# led_RGB.net
KiCad netlist of a schematic drawn in Altium Designer
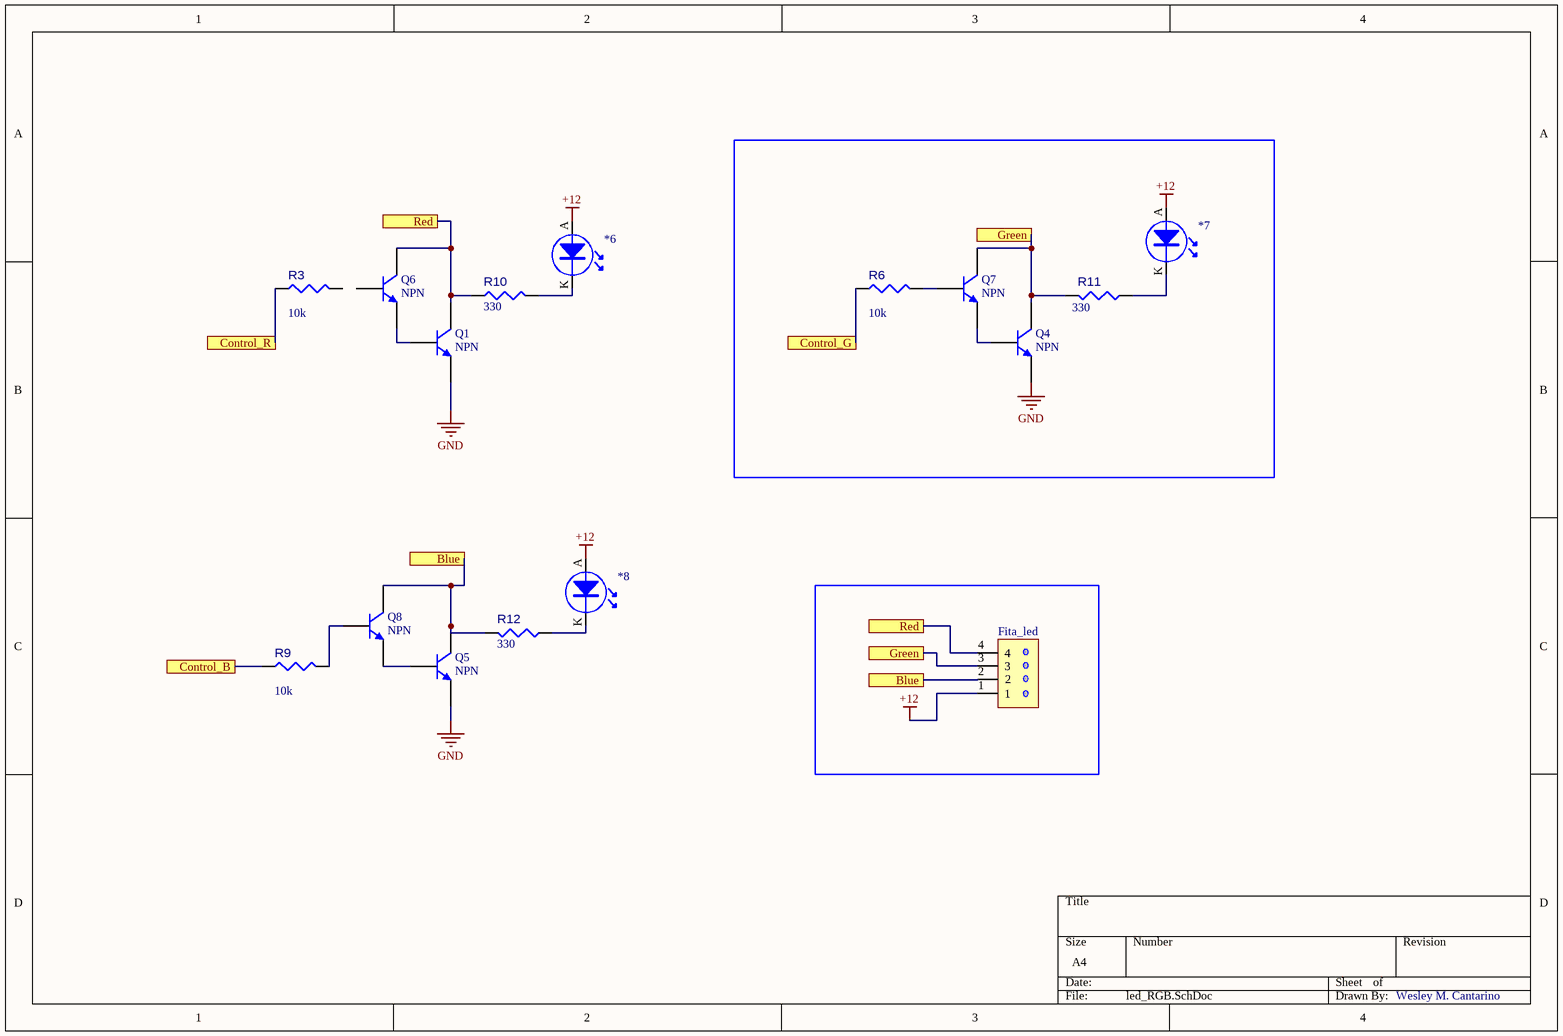
[diagram p0: led_RGB.SchDoc]

(export (version "E")
  (design (tool "Eeschema 10.0.6"))
  (components
    (comp (ref "*6")
      (value "LED_AXIAL_5MM")
      (footprint "HEADER_1X2")
      (libsource (lib "i9Library_Altium") (part "LED_AXIAL_5MM"))
    )
    (comp (ref "*7")
      (value "LED_AXIAL_5MM")
      (footprint "HEADER_1X2")
      (libsource (lib "i9Library_Altium") (part "LED_AXIAL_5MM"))
    )
    (comp (ref "*8")
      (value "LED_AXIAL_5MM")
      (footprint "HEADER_1X2")
      (libsource (lib "i9Library_Altium") (part "LED_AXIAL_5MM"))
    )
    (comp (ref "Fita_led")
      (value "CN_KK_4")
      (footprint "CN_KK_4_5045-4")
      (description "KK_4")
      (libsource (lib "i9Library_Altium") (part "CN_KK_4"))
    )
    (comp (ref "Q1")
      (value "NPN")
      (footprint "HEADER_1X3")
      (description "NPN Bipolar Transistor")
      (fields (field (name "PUBLISHER") "Altium Limited"))
      (libsource (lib "Miscellaneous Devices") (part "NPN"))
    )
    (comp (ref "Q4")
      (value "NPN")
      (footprint "HEADER_1X3")
      (description "NPN Bipolar Transistor")
      (fields (field (name "PUBLISHER") "Altium Limited"))
      (libsource (lib "Miscellaneous Devices") (part "NPN"))
    )
    (comp (ref "Q5")
      (value "NPN")
      (footprint "HEADER_1X3")
      (description "NPN Bipolar Transistor")
      (fields (field (name "PUBLISHER") "Altium Limited"))
      (libsource (lib "Miscellaneous Devices") (part "NPN"))
    )
    (comp (ref "Q6")
      (value "NPN")
      (footprint "HEADER_1X3")
      (description "NPN Bipolar Transistor")
      (fields (field (name "PUBLISHER") "Altium Limited"))
      (libsource (lib "Miscellaneous Devices") (part "NPN"))
    )
    (comp (ref "Q7")
      (value "NPN")
      (footprint "HEADER_1X3")
      (description "NPN Bipolar Transistor")
      (fields (field (name "PUBLISHER") "Altium Limited"))
      (libsource (lib "Miscellaneous Devices") (part "NPN"))
    )
    (comp (ref "Q8")
      (value "NPN")
      (footprint "HEADER_1X3")
      (description "NPN Bipolar Transistor")
      (fields (field (name "PUBLISHER") "Altium Limited"))
      (libsource (lib "Miscellaneous Devices") (part "NPN"))
    )
    (comp (ref "R3")
      (value "10k")
      (footprint "RES_PTH_7.62MM")
      (description "Pin Through Hole Resistor 7.62mm")
      (libsource (lib "i9Library_Altium") (part "RES_PTH_7.62MM"))
    )
    (comp (ref "R6")
      (value "10k")
      (footprint "RES_PTH_7.62MM")
      (description "Pin Through Hole Resistor 7.62mm")
      (libsource (lib "i9Library_Altium") (part "RES_PTH_7.62MM"))
    )
    (comp (ref "R9")
      (value "10k")
      (footprint "RES_PTH_7.62MM")
      (description "Pin Through Hole Resistor 7.62mm")
      (libsource (lib "i9Library_Altium") (part "RES_PTH_7.62MM"))
    )
    (comp (ref "R10")
      (value "330")
      (footprint "RES_PTH_7.62MM")
      (description "Pin Through Hole Resistor 7.62mm")
      (libsource (lib "i9Library_Altium") (part "RES_PTH_7.62MM"))
    )
    (comp (ref "R11")
      (value "330")
      (footprint "RES_PTH_7.62MM")
      (description "Pin Through Hole Resistor 7.62mm")
      (libsource (lib "i9Library_Altium") (part "RES_PTH_7.62MM"))
    )
    (comp (ref "R12")
      (value "330")
      (footprint "RES_PTH_7.62MM")
      (description "Pin Through Hole Resistor 7.62mm")
      (libsource (lib "i9Library_Altium") (part "RES_PTH_7.62MM"))
    )
  )
  (nets
    (net (code "1") (name "+12") (class "Default")
      (node (ref "*6") (pin "A") (pintype "passive"))
      (node (ref "*7") (pin "A") (pintype "passive"))
      (node (ref "*8") (pin "A") (pintype "passive"))
      (node (ref "Fita_led") (pin "1") (pinfunction "1_1") (pintype "passive"))
    )
    (net (code "2") (name "/Blue") (class "Default")
      (node (ref "Fita_led") (pin "2") (pinfunction "2_2") (pintype "passive"))
      (node (ref "Q5") (pin "1") (pinfunction "C_1") (pintype "passive"))
      (node (ref "Q8") (pin "1") (pinfunction "C_1") (pintype "passive"))
      (node (ref "R12") (pin "2") (pinfunction "2_2") (pintype "passive"))
    )
    (net (code "3") (name "/Control_B") (class "Default")
      (node (ref "R9") (pin "1") (pinfunction "1_1") (pintype "passive"))
    )
    (net (code "4") (name "/Control_G") (class "Default")
      (node (ref "R6") (pin "1") (pinfunction "1_1") (pintype "passive"))
    )
    (net (code "5") (name "/Control_R") (class "Default")
      (node (ref "R3") (pin "1") (pinfunction "1_1") (pintype "passive"))
    )
    (net (code "6") (name "/Green") (class "Default")
      (node (ref "Fita_led") (pin "3") (pinfunction "3_3") (pintype "passive"))
      (node (ref "Q4") (pin "1") (pinfunction "C_1") (pintype "passive"))
      (node (ref "Q7") (pin "1") (pinfunction "C_1") (pintype "passive"))
      (node (ref "R11") (pin "2") (pinfunction "2_2") (pintype "passive"))
    )
    (net (code "7") (name "/Red") (class "Default")
      (node (ref "Fita_led") (pin "4") (pinfunction "4_4") (pintype "passive"))
      (node (ref "Q1") (pin "1") (pinfunction "C_1") (pintype "passive"))
      (node (ref "Q6") (pin "1") (pinfunction "C_1") (pintype "passive"))
      (node (ref "R10") (pin "1") (pinfunction "1_1") (pintype "passive"))
    )
    (net (code "8") (name "GND") (class "Default")
      (node (ref "Q1") (pin "3") (pinfunction "E_3") (pintype "passive"))
      (node (ref "Q4") (pin "3") (pinfunction "E_3") (pintype "passive"))
      (node (ref "Q5") (pin "3") (pinfunction "E_3") (pintype "passive"))
    )
    (net (code "9") (name "Net-(*6-PadK)") (class "Default")
      (node (ref "*6") (pin "K") (pintype "passive"))
      (node (ref "R10") (pin "2") (pinfunction "2_2") (pintype "passive"))
    )
    (net (code "10") (name "Net-(*7-PadK)") (class "Default")
      (node (ref "*7") (pin "K") (pintype "passive"))
      (node (ref "R11") (pin "1") (pinfunction "1_1") (pintype "passive"))
    )
    (net (code "11") (name "Net-(*8-PadK)") (class "Default")
      (node (ref "*8") (pin "K") (pintype "passive"))
      (node (ref "R12") (pin "1") (pinfunction "1_1") (pintype "passive"))
    )
    (net (code "12") (name "Net-(Q1-B)") (class "Default")
      (node (ref "Q1") (pin "2") (pinfunction "B_2") (pintype "passive"))
      (node (ref "Q6") (pin "3") (pinfunction "E_3") (pintype "passive"))
    )
    (net (code "13") (name "Net-(Q4-B)") (class "Default")
      (node (ref "Q4") (pin "2") (pinfunction "B_2") (pintype "passive"))
      (node (ref "Q7") (pin "3") (pinfunction "E_3") (pintype "passive"))
    )
    (net (code "14") (name "Net-(Q5-B)") (class "Default")
      (node (ref "Q5") (pin "2") (pinfunction "B_2") (pintype "passive"))
      (node (ref "Q8") (pin "3") (pinfunction "E_3") (pintype "passive"))
    )
    (net (code "15") (name "Net-(Q7-B)") (class "Default")
      (node (ref "Q7") (pin "2") (pinfunction "B_2") (pintype "passive"))
      (node (ref "R6") (pin "2") (pinfunction "2_2") (pintype "passive"))
    )
    (net (code "16") (name "Net-(Q8-B)") (class "Default")
      (node (ref "Q8") (pin "2") (pinfunction "B_2") (pintype "passive"))
      (node (ref "R9") (pin "2") (pinfunction "2_2") (pintype "passive"))
    )
    (net (code "17") (name "unconnected-(Q6-B-Pad2)") (class "Default")
      (node (ref "Q6") (pin "2") (pinfunction "B_2") (pintype "passive"))
    )
    (net (code "18") (name "unconnected-(R3-Pad2)") (class "Default")
      (node (ref "R3") (pin "2") (pinfunction "2_2") (pintype "passive"))
    )
  )
)
